# Aux_Board_V3.net
KiCad netlist of a schematic drawn in EAGLE
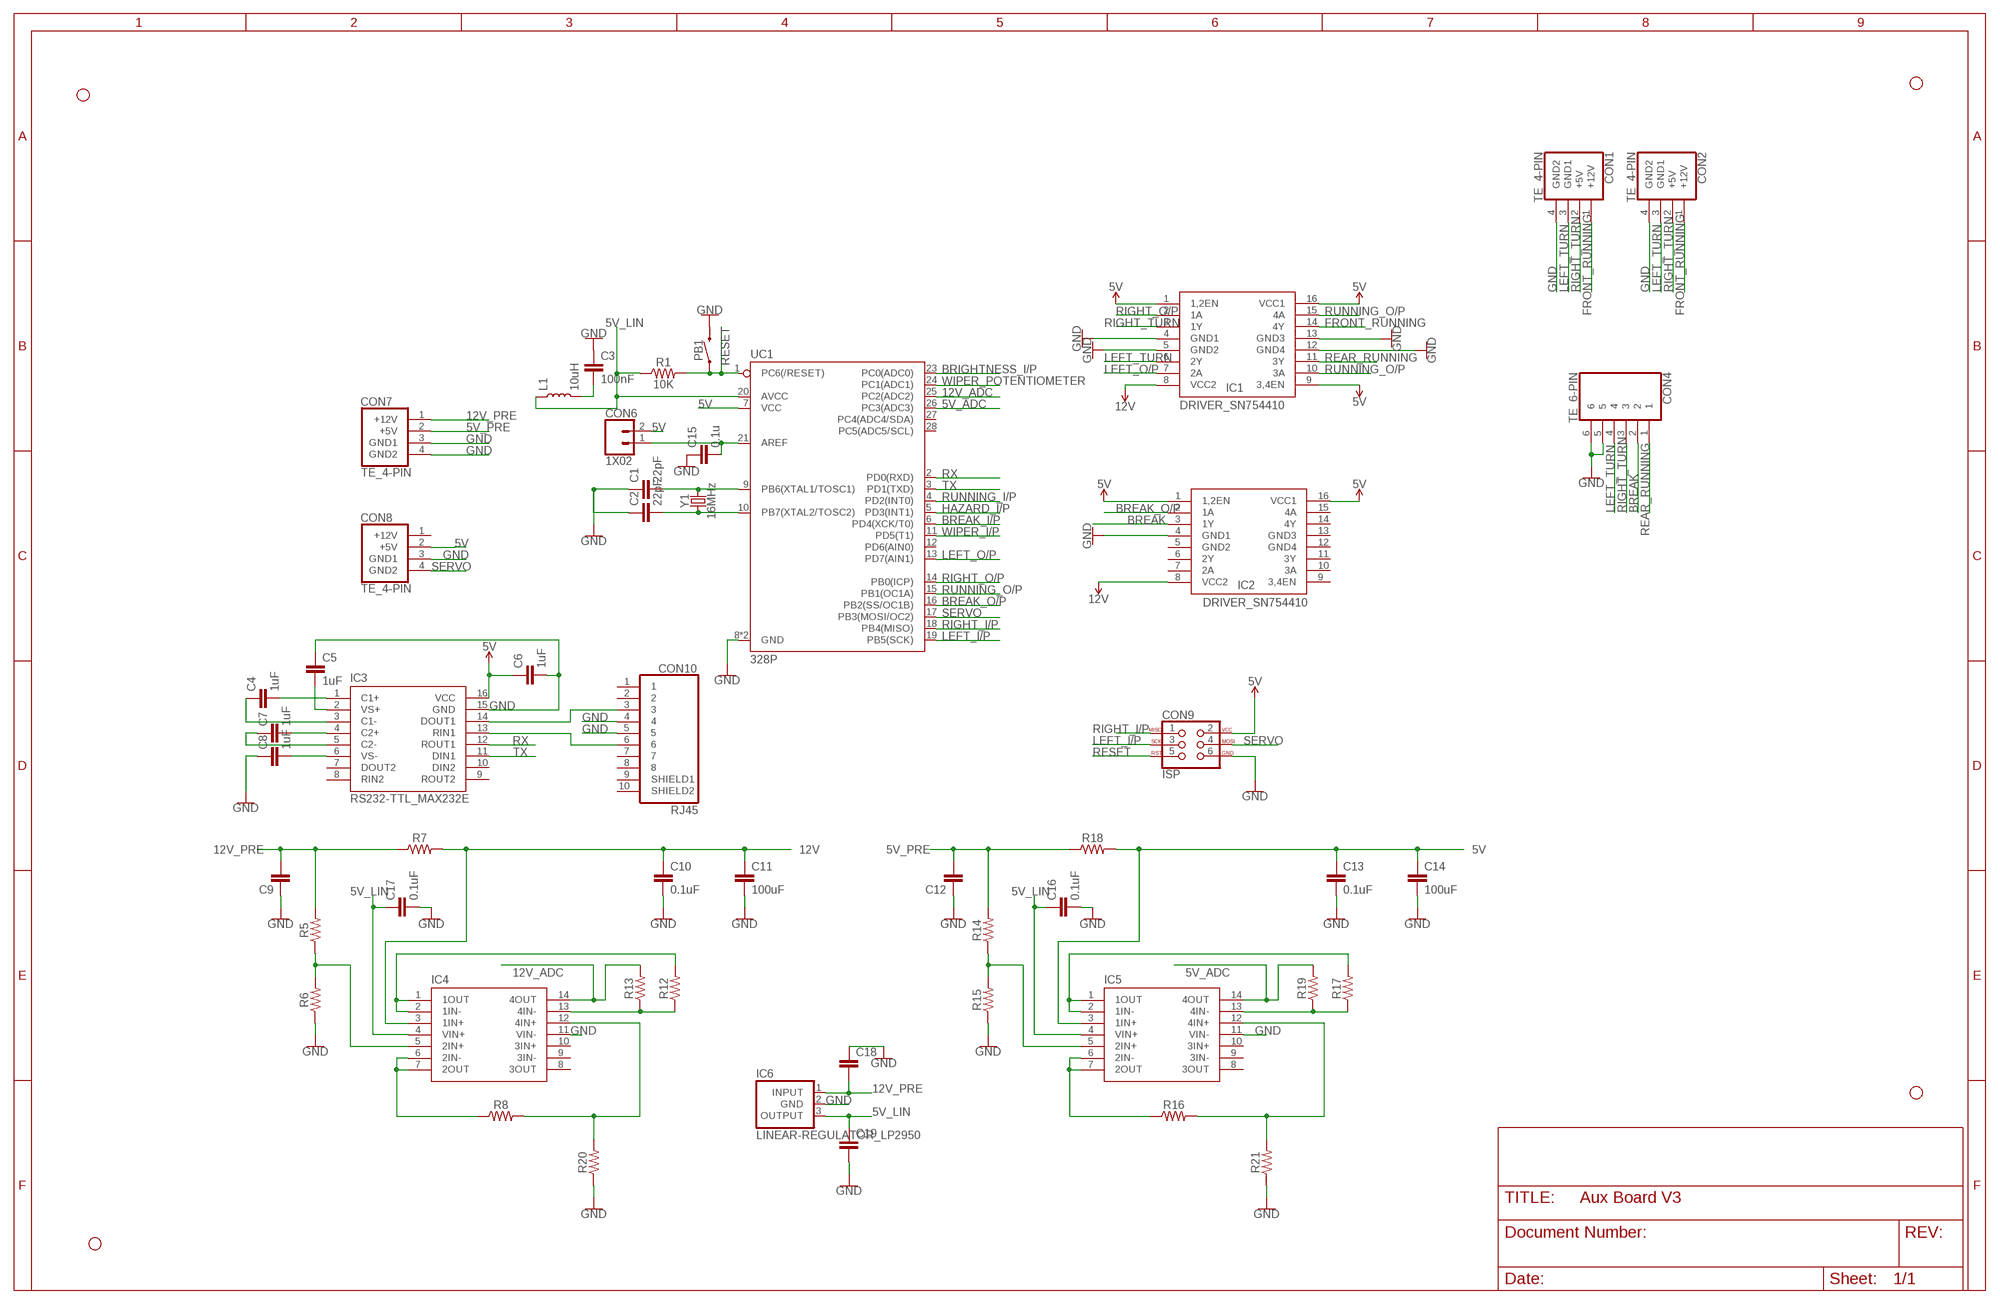
[diagram p0: schematic, sheet 1]

(export (version "E")
  (design (tool "Eeschema 10.0.6"))
  (components
    (comp (ref "C1")
      (value "22pF")
      (footprint "eagle-import:0805")
      (libsource (lib "eagle-import") (part "CAPACITOR_0805"))
    )
    (comp (ref "C2")
      (value "22pF")
      (footprint "eagle-import:0805")
      (libsource (lib "eagle-import") (part "CAPACITOR_0805"))
    )
    (comp (ref "C3")
      (value "100nF")
      (footprint "eagle-import:0805")
      (libsource (lib "eagle-import") (part "CAPACITOR_0805"))
    )
    (comp (ref "C4")
      (value "1uF")
      (footprint "eagle-import:0805")
      (libsource (lib "eagle-import") (part "CAPACITOR_0805"))
    )
    (comp (ref "C5")
      (value "1uF")
      (footprint "eagle-import:0805")
      (libsource (lib "eagle-import") (part "CAPACITOR_0805"))
    )
    (comp (ref "C6")
      (value "1uF")
      (footprint "eagle-import:0805")
      (libsource (lib "eagle-import") (part "CAPACITOR_0805"))
    )
    (comp (ref "C7")
      (value "1uF")
      (footprint "eagle-import:0805")
      (libsource (lib "eagle-import") (part "CAPACITOR_0805"))
    )
    (comp (ref "C8")
      (value "1uF")
      (footprint "eagle-import:0805")
      (libsource (lib "eagle-import") (part "CAPACITOR_0805"))
    )
    (comp (ref "C9")
      (value "CAPACITOR_0805")
      (footprint "eagle-import:0805")
      (libsource (lib "eagle-import") (part "CAPACITOR_0805"))
    )
    (comp (ref "C10")
      (value "0.1uF")
      (footprint "eagle-import:0805")
      (libsource (lib "eagle-import") (part "CAPACITOR_0805"))
    )
    (comp (ref "C11")
      (value "100uF")
      (footprint "eagle-import:0805")
      (libsource (lib "eagle-import") (part "CAPACITOR_0805"))
    )
    (comp (ref "C12")
      (value "CAPACITOR_0805")
      (footprint "eagle-import:0805")
      (libsource (lib "eagle-import") (part "CAPACITOR_0805"))
    )
    (comp (ref "C13")
      (value "0.1uF")
      (footprint "eagle-import:0805")
      (libsource (lib "eagle-import") (part "CAPACITOR_0805"))
    )
    (comp (ref "C14")
      (value "100uF")
      (footprint "eagle-import:0805")
      (libsource (lib "eagle-import") (part "CAPACITOR_0805"))
    )
    (comp (ref "C15")
      (value "0.1u")
      (footprint "eagle-import:0805")
      (libsource (lib "eagle-import") (part "CAPACITOR_0805"))
    )
    (comp (ref "C16")
      (value "0.1uF")
      (footprint "eagle-import:0805")
      (libsource (lib "eagle-import") (part "CAPACITOR_0805"))
    )
    (comp (ref "C17")
      (value "0.1uF")
      (footprint "eagle-import:0805")
      (libsource (lib "eagle-import") (part "CAPACITOR_0805"))
    )
    (comp (ref "C18")
      (value "CAPACITOR_0805")
      (footprint "eagle-import:0805")
      (libsource (lib "eagle-import") (part "CAPACITOR_0805"))
    )
    (comp (ref "C19")
      (value "CAPACITOR_0805")
      (footprint "eagle-import:0805")
      (libsource (lib "eagle-import") (part "CAPACITOR_0805"))
    )
    (comp (ref "CON1")
      (value "TE_4-PIN")
      (footprint "eagle-import:TE_4-PIN")
      (libsource (lib "eagle-import") (part "TE_4-PIN"))
    )
    (comp (ref "CON2")
      (value "TE_4-PIN")
      (footprint "eagle-import:TE_4-PIN")
      (libsource (lib "eagle-import") (part "TE_4-PIN"))
    )
    (comp (ref "CON4")
      (value "TE_6-PIN")
      (footprint "eagle-import:TE_6-PIN")
      (libsource (lib "eagle-import") (part "TE_6-PIN"))
    )
    (comp (ref "CON6")
      (value "1X02")
      (footprint "eagle-import:1X02")
      (libsource (lib "eagle-import") (part "1X02"))
    )
    (comp (ref "CON7")
      (value "TE_4-PIN")
      (footprint "eagle-import:TE_4-PIN")
      (libsource (lib "eagle-import") (part "TE_4-PIN"))
    )
    (comp (ref "CON8")
      (value "TE_4-PIN")
      (footprint "eagle-import:TE_4-PIN")
      (libsource (lib "eagle-import") (part "TE_4-PIN"))
    )
    (comp (ref "CON9")
      (value "ISP")
      (footprint "eagle-import:ISP_CONNECTOR")
      (libsource (lib "eagle-import") (part "ISP"))
    )
    (comp (ref "CON10")
      (value "RJ45")
      (footprint "eagle-import:RJ45")
      (libsource (lib "eagle-import") (part "RJ45"))
    )
    (comp (ref "H1")
      (value "STAND-OFF")
      (footprint "eagle-import:STAND-OFF")
      (libsource (lib "eagle-import") (part "STAND-OFF"))
    )
    (comp (ref "H2")
      (value "STAND-OFF")
      (footprint "eagle-import:STAND-OFF")
      (libsource (lib "eagle-import") (part "STAND-OFF"))
    )
    (comp (ref "H3")
      (value "STAND-OFF")
      (footprint "eagle-import:STAND-OFF")
      (libsource (lib "eagle-import") (part "STAND-OFF"))
    )
    (comp (ref "H4")
      (value "STAND-OFF")
      (footprint "eagle-import:STAND-OFF")
      (libsource (lib "eagle-import") (part "STAND-OFF"))
    )
    (comp (ref "IC1")
      (value "DRIVER_SN754410")
      (footprint "eagle-import:DIP16")
      (libsource (lib "eagle-import") (part "DRIVER_SN754410"))
    )
    (comp (ref "IC2")
      (value "DRIVER_SN754410")
      (footprint "eagle-import:DIP16")
      (libsource (lib "eagle-import") (part "DRIVER_SN754410"))
    )
    (comp (ref "IC3")
      (value "RS232-TTL_MAX232E")
      (footprint "eagle-import:DIP16")
      (libsource (lib "eagle-import") (part "RS232-TTL_MAX232E"))
    )
    (comp (ref "IC4")
      (value "OP-AMP_QUAD")
      (footprint "eagle-import:DIP14")
      (libsource (lib "eagle-import") (part "OP-AMP_QUAD"))
    )
    (comp (ref "IC5")
      (value "OP-AMP_QUAD")
      (footprint "eagle-import:DIP14")
      (libsource (lib "eagle-import") (part "OP-AMP_QUAD"))
    )
    (comp (ref "IC6")
      (value "LINEAR-REGULATOR_LP2950")
      (footprint "eagle-import:TO92")
      (libsource (lib "eagle-import") (part "LINEAR-REGULATOR_LP2950"))
    )
    (comp (ref "L1")
      (value "10uH")
      (footprint "eagle-import:0805")
      (libsource (lib "eagle-import") (part "INDUCTOR_0805"))
    )
    (comp (ref "PB1")
      (value "PUSHBUTTON")
      (footprint "eagle-import:PUSHBUTTON")
      (libsource (lib "eagle-import") (part "PUSHBUTTON"))
    )
    (comp (ref "R1")
      (value "10K")
      (footprint "eagle-import:0805")
      (libsource (lib "eagle-import") (part "RESISTOR_0805"))
    )
    (comp (ref "R5")
      (value "RESISTOR_0805")
      (footprint "eagle-import:0805")
      (libsource (lib "eagle-import") (part "RESISTOR_0805"))
    )
    (comp (ref "R6")
      (value "RESISTOR_0805")
      (footprint "eagle-import:0805")
      (libsource (lib "eagle-import") (part "RESISTOR_0805"))
    )
    (comp (ref "R7")
      (value "RESISTOR_1210")
      (footprint "eagle-import:1210")
      (libsource (lib "eagle-import") (part "RESISTOR_1210"))
    )
    (comp (ref "R8")
      (value "RESISTOR_0805")
      (footprint "eagle-import:0805")
      (libsource (lib "eagle-import") (part "RESISTOR_0805"))
    )
    (comp (ref "R12")
      (value "RESISTOR_0805")
      (footprint "eagle-import:0805")
      (libsource (lib "eagle-import") (part "RESISTOR_0805"))
    )
    (comp (ref "R13")
      (value "RESISTOR_0805")
      (footprint "eagle-import:0805")
      (libsource (lib "eagle-import") (part "RESISTOR_0805"))
    )
    (comp (ref "R14")
      (value "RESISTOR_0805")
      (footprint "eagle-import:0805")
      (libsource (lib "eagle-import") (part "RESISTOR_0805"))
    )
    (comp (ref "R15")
      (value "RESISTOR_0805")
      (footprint "eagle-import:0805")
      (libsource (lib "eagle-import") (part "RESISTOR_0805"))
    )
    (comp (ref "R16")
      (value "RESISTOR_0805")
      (footprint "eagle-import:0805")
      (libsource (lib "eagle-import") (part "RESISTOR_0805"))
    )
    (comp (ref "R17")
      (value "RESISTOR_0805")
      (footprint "eagle-import:0805")
      (libsource (lib "eagle-import") (part "RESISTOR_0805"))
    )
    (comp (ref "R18")
      (value "RESISTOR_1210")
      (footprint "eagle-import:1210")
      (libsource (lib "eagle-import") (part "RESISTOR_1210"))
    )
    (comp (ref "R19")
      (value "RESISTOR_0805")
      (footprint "eagle-import:0805")
      (libsource (lib "eagle-import") (part "RESISTOR_0805"))
    )
    (comp (ref "R20")
      (value "RESISTOR_0805")
      (footprint "eagle-import:0805")
      (libsource (lib "eagle-import") (part "RESISTOR_0805"))
    )
    (comp (ref "R21")
      (value "RESISTOR_0805")
      (footprint "eagle-import:0805")
      (libsource (lib "eagle-import") (part "RESISTOR_0805"))
    )
    (comp (ref "UC1")
      (value "328P")
      (footprint "eagle-import:DIP28")
      (libsource (lib "eagle-import") (part "ATMEGA328P_DIP28"))
    )
    (comp (ref "Y1")
      (value "16MHz")
      (footprint "eagle-import:HC49US")
      (libsource (lib "eagle-import") (part "CRYSTAL-16MHZPTH-HC49US"))
    )
  )
  (nets
    (net (code "1") (name "/5V_ADC") (class "Default")
      (node (ref "IC5") (pin "14") (pinfunction "4OUT_14") (pintype "bidirectional"))
      (node (ref "R19") (pin "2") (pinfunction "2_2") (pintype "passive"))
      (node (ref "UC1") (pin "26") (pinfunction "PC3(ADC3)_26") (pintype "bidirectional"))
    )
    (net (code "2") (name "/5V_LIN") (class "Default")
      (node (ref "C16") (pin "1") (pinfunction "1_1") (pintype "passive"))
      (node (ref "C17") (pin "1") (pinfunction "1_1") (pintype "passive"))
      (node (ref "C19") (pin "1") (pinfunction "1_1") (pintype "passive"))
      (node (ref "IC4") (pin "4") (pinfunction "VIN+_4") (pintype "bidirectional"))
      (node (ref "IC5") (pin "4") (pinfunction "VIN+_4") (pintype "bidirectional"))
      (node (ref "IC6") (pin "3") (pinfunction "OUTPUT_3") (pintype "bidirectional"))
      (node (ref "L1") (pin "1") (pinfunction "1_1") (pintype "passive"))
      (node (ref "R1") (pin "1") (pinfunction "1_1") (pintype "passive"))
      (node (ref "UC1") (pin "20") (pinfunction "AVCC_20") (pintype "bidirectional"))
    )
    (net (code "3") (name "/5V_PRE") (class "Default")
      (node (ref "C12") (pin "2") (pinfunction "2_2") (pintype "passive"))
      (node (ref "CON7") (pin "2") (pinfunction "+5V_2") (pintype "passive"))
      (node (ref "R14") (pin "2") (pinfunction "2_2") (pintype "passive"))
      (node (ref "R18") (pin "1") (pinfunction "1_1") (pintype "passive"))
    )
    (net (code "4") (name "/12V_ADC") (class "Default")
      (node (ref "IC4") (pin "14") (pinfunction "4OUT_14") (pintype "bidirectional"))
      (node (ref "R13") (pin "2") (pinfunction "2_2") (pintype "passive"))
      (node (ref "UC1") (pin "25") (pinfunction "PC2(ADC2)_25") (pintype "bidirectional"))
    )
    (net (code "5") (name "/12V_PRE") (class "Default")
      (node (ref "C18") (pin "2") (pinfunction "2_2") (pintype "passive"))
      (node (ref "C9") (pin "2") (pinfunction "2_2") (pintype "passive"))
      (node (ref "CON7") (pin "1") (pinfunction "+12V_1") (pintype "passive"))
      (node (ref "IC6") (pin "1") (pinfunction "INPUT_1") (pintype "bidirectional"))
      (node (ref "R5") (pin "2") (pinfunction "2_2") (pintype "passive"))
      (node (ref "R7") (pin "1") (pinfunction "1_1") (pintype "passive"))
    )
    (net (code "6") (name "/BREAK") (class "Default")
      (node (ref "CON4") (pin "2") (pinfunction "2_2") (pintype "passive"))
      (node (ref "IC2") (pin "3") (pinfunction "1Y_3") (pintype "bidirectional"))
    )
    (net (code "7") (name "/BREAK_I{slash}P") (class "Default")
      (node (ref "UC1") (pin "6") (pinfunction "PD4(XCK/T0)_6") (pintype "bidirectional"))
    )
    (net (code "8") (name "/BREAK_O{slash}P") (class "Default")
      (node (ref "IC2") (pin "2") (pinfunction "1A_2") (pintype "bidirectional"))
      (node (ref "UC1") (pin "16") (pinfunction "PB2(SS/OC1B)_16") (pintype "bidirectional"))
    )
    (net (code "9") (name "/BRIGHTNESS_I{slash}P") (class "Default")
      (node (ref "UC1") (pin "23") (pinfunction "PC0(ADC0)_23") (pintype "bidirectional"))
    )
    (net (code "10") (name "/FRONT_RUNNING") (class "Default")
      (node (ref "CON1") (pin "1") (pinfunction "+12V_1") (pintype "passive"))
      (node (ref "CON2") (pin "1") (pinfunction "+12V_1") (pintype "passive"))
      (node (ref "IC1") (pin "14") (pinfunction "4Y_14") (pintype "bidirectional"))
    )
    (net (code "11") (name "/HAZARD_I{slash}P") (class "Default")
      (node (ref "UC1") (pin "5") (pinfunction "PD3(INT1)_5") (pintype "bidirectional"))
    )
    (net (code "12") (name "/LEFT_I{slash}P") (class "Default")
      (node (ref "CON9") (pin "3") (pinfunction "3_3") (pintype "passive"))
      (node (ref "UC1") (pin "19") (pinfunction "PB5(SCK)_19") (pintype "bidirectional"))
    )
    (net (code "13") (name "/LEFT_O{slash}P") (class "Default")
      (node (ref "IC1") (pin "7") (pinfunction "2A_7") (pintype "bidirectional"))
      (node (ref "UC1") (pin "13") (pinfunction "PD7(AIN1)_13") (pintype "bidirectional"))
    )
    (net (code "14") (name "/LEFT_TURN") (class "Default")
      (node (ref "CON1") (pin "3") (pinfunction "GND1_3") (pintype "passive"))
      (node (ref "CON2") (pin "3") (pinfunction "GND1_3") (pintype "passive"))
      (node (ref "CON4") (pin "4") (pinfunction "4_4") (pintype "passive"))
      (node (ref "IC1") (pin "6") (pinfunction "2Y_6") (pintype "bidirectional"))
    )
    (net (code "15") (name "/REAR_RUNNING") (class "Default")
      (node (ref "CON4") (pin "1") (pinfunction "1_1") (pintype "passive"))
      (node (ref "IC1") (pin "11") (pinfunction "3Y_11") (pintype "bidirectional"))
    )
    (net (code "16") (name "/RESET") (class "Default")
      (node (ref "CON9") (pin "5") (pinfunction "5_5") (pintype "passive"))
      (node (ref "PB1") (pin "1") (pinfunction "1_1") (pintype "passive"))
      (node (ref "PB1") (pin "2") (pinfunction "1_2") (pintype "passive"))
      (node (ref "R1") (pin "2") (pinfunction "2_2") (pintype "passive"))
      (node (ref "UC1") (pin "1") (pinfunction "PC6(/RESET)_1") (pintype "bidirectional"))
    )
    (net (code "17") (name "/RIGHT_I{slash}P") (class "Default")
      (node (ref "CON9") (pin "1") (pinfunction "1_1") (pintype "passive"))
      (node (ref "UC1") (pin "18") (pinfunction "PB4(MISO)_18") (pintype "bidirectional"))
    )
    (net (code "18") (name "/RIGHT_O{slash}P") (class "Default")
      (node (ref "IC1") (pin "2") (pinfunction "1A_2") (pintype "bidirectional"))
      (node (ref "UC1") (pin "14") (pinfunction "PB0(ICP)_14") (pintype "bidirectional"))
    )
    (net (code "19") (name "/RIGHT_TURN") (class "Default")
      (node (ref "CON1") (pin "2") (pinfunction "+5V_2") (pintype "passive"))
      (node (ref "CON2") (pin "2") (pinfunction "+5V_2") (pintype "passive"))
      (node (ref "CON4") (pin "3") (pinfunction "3_3") (pintype "passive"))
      (node (ref "IC1") (pin "3") (pinfunction "1Y_3") (pintype "bidirectional"))
    )
    (net (code "20") (name "/RUNNING_I{slash}P") (class "Default")
      (node (ref "UC1") (pin "4") (pinfunction "PD2(INT0)_4") (pintype "bidirectional"))
    )
    (net (code "21") (name "/RUNNING_O{slash}P") (class "Default")
      (node (ref "IC1") (pin "10") (pinfunction "3A_10") (pintype "bidirectional"))
      (node (ref "IC1") (pin "15") (pinfunction "4A_15") (pintype "bidirectional"))
      (node (ref "UC1") (pin "15") (pinfunction "PB1(OC1A)_15") (pintype "bidirectional"))
    )
    (net (code "22") (name "/RX") (class "Default")
      (node (ref "IC3") (pin "12") (pinfunction "ROUT1_12") (pintype "bidirectional"))
      (node (ref "UC1") (pin "2") (pinfunction "PD0(RXD)_2") (pintype "bidirectional"))
    )
    (net (code "23") (name "/SERVO") (class "Default")
      (node (ref "CON8") (pin "4") (pinfunction "GND2_4") (pintype "passive"))
      (node (ref "CON9") (pin "4") (pinfunction "4_4") (pintype "passive"))
      (node (ref "UC1") (pin "17") (pinfunction "PB3(MOSI/OC2)_17") (pintype "bidirectional"))
    )
    (net (code "24") (name "/TX") (class "Default")
      (node (ref "IC3") (pin "11") (pinfunction "DIN1_11") (pintype "bidirectional"))
      (node (ref "UC1") (pin "3") (pinfunction "PD1(TXD)_3") (pintype "bidirectional"))
    )
    (net (code "25") (name "/WIPER_I{slash}P") (class "Default")
      (node (ref "UC1") (pin "11") (pinfunction "PD5(T1)_11") (pintype "bidirectional"))
    )
    (net (code "26") (name "/WIPER_POTENTIOMETER") (class "Default")
      (node (ref "UC1") (pin "24") (pinfunction "PC1(ADC1)_24") (pintype "bidirectional"))
    )
    (net (code "27") (name "5V") (class "Default")
      (node (ref "C13") (pin "1") (pinfunction "1_1") (pintype "passive"))
      (node (ref "C14") (pin "1") (pinfunction "1_1") (pintype "passive"))
      (node (ref "C15") (pin "2") (pinfunction "2_2") (pintype "passive"))
      (node (ref "C6") (pin "1") (pinfunction "1_1") (pintype "passive"))
      (node (ref "CON6") (pin "1") (pinfunction "1_1") (pintype "passive"))
      (node (ref "CON6") (pin "2") (pinfunction "2_2") (pintype "passive"))
      (node (ref "CON8") (pin "2") (pinfunction "+5V_2") (pintype "passive"))
      (node (ref "CON9") (pin "2") (pinfunction "2_2") (pintype "passive"))
      (node (ref "IC1") (pin "1") (pinfunction "1,2EN_1") (pintype "bidirectional"))
      (node (ref "IC1") (pin "16") (pinfunction "VCC1_16") (pintype "bidirectional"))
      (node (ref "IC1") (pin "9") (pinfunction "3,4EN_9") (pintype "bidirectional"))
      (node (ref "IC2") (pin "1") (pinfunction "1,2EN_1") (pintype "bidirectional"))
      (node (ref "IC2") (pin "16") (pinfunction "VCC1_16") (pintype "bidirectional"))
      (node (ref "IC3") (pin "16") (pinfunction "VCC_16") (pintype "bidirectional"))
      (node (ref "IC5") (pin "3") (pinfunction "1IN+_3") (pintype "bidirectional"))
      (node (ref "R18") (pin "2") (pinfunction "2_2") (pintype "passive"))
      (node (ref "UC1") (pin "21") (pinfunction "AREF_21") (pintype "bidirectional"))
      (node (ref "UC1") (pin "7") (pinfunction "VCC_7") (pintype "bidirectional"))
    )
    (net (code "28") (name "12V") (class "Default")
      (node (ref "C10") (pin "1") (pinfunction "1_1") (pintype "passive"))
      (node (ref "C11") (pin "1") (pinfunction "1_1") (pintype "passive"))
      (node (ref "IC1") (pin "8") (pinfunction "VCC2_8") (pintype "bidirectional"))
      (node (ref "IC2") (pin "8") (pinfunction "VCC2_8") (pintype "bidirectional"))
      (node (ref "IC4") (pin "3") (pinfunction "1IN+_3") (pintype "bidirectional"))
      (node (ref "R7") (pin "2") (pinfunction "2_2") (pintype "passive"))
    )
    (net (code "29") (name "GND") (class "Default")
      (node (ref "C1") (pin "1") (pinfunction "1_1") (pintype "passive"))
      (node (ref "C10") (pin "2") (pinfunction "2_2") (pintype "passive"))
      (node (ref "C11") (pin "2") (pinfunction "2_2") (pintype "passive"))
      (node (ref "C12") (pin "1") (pinfunction "1_1") (pintype "passive"))
      (node (ref "C13") (pin "2") (pinfunction "2_2") (pintype "passive"))
      (node (ref "C14") (pin "2") (pinfunction "2_2") (pintype "passive"))
      (node (ref "C15") (pin "1") (pinfunction "1_1") (pintype "passive"))
      (node (ref "C16") (pin "2") (pinfunction "2_2") (pintype "passive"))
      (node (ref "C17") (pin "2") (pinfunction "2_2") (pintype "passive"))
      (node (ref "C18") (pin "1") (pinfunction "1_1") (pintype "passive"))
      (node (ref "C19") (pin "2") (pinfunction "2_2") (pintype "passive"))
      (node (ref "C2") (pin "1") (pinfunction "1_1") (pintype "passive"))
      (node (ref "C3") (pin "1") (pinfunction "1_1") (pintype "passive"))
      (node (ref "C5") (pin "1") (pinfunction "1_1") (pintype "passive"))
      (node (ref "C6") (pin "2") (pinfunction "2_2") (pintype "passive"))
      (node (ref "C8") (pin "1") (pinfunction "1_1") (pintype "passive"))
      (node (ref "C9") (pin "1") (pinfunction "1_1") (pintype "passive"))
      (node (ref "CON1") (pin "4") (pinfunction "GND2_4") (pintype "passive"))
      (node (ref "CON10") (pin "4") (pinfunction "4_4") (pintype "passive"))
      (node (ref "CON10") (pin "5") (pinfunction "5_5") (pintype "passive"))
      (node (ref "CON2") (pin "4") (pinfunction "GND2_4") (pintype "passive"))
      (node (ref "CON4") (pin "5") (pinfunction "5_5") (pintype "passive"))
      (node (ref "CON4") (pin "6") (pinfunction "6_6") (pintype "passive"))
      (node (ref "CON7") (pin "3") (pinfunction "GND1_3") (pintype "passive"))
      (node (ref "CON7") (pin "4") (pinfunction "GND2_4") (pintype "passive"))
      (node (ref "CON8") (pin "3") (pinfunction "GND1_3") (pintype "passive"))
      (node (ref "CON9") (pin "6") (pinfunction "6_6") (pintype "passive"))
      (node (ref "IC1") (pin "12") (pinfunction "GND4_12") (pintype "bidirectional"))
      (node (ref "IC1") (pin "13") (pinfunction "GND3_13") (pintype "bidirectional"))
      (node (ref "IC1") (pin "4") (pinfunction "GND1_4") (pintype "bidirectional"))
      (node (ref "IC1") (pin "5") (pinfunction "GND2_5") (pintype "bidirectional"))
      (node (ref "IC2") (pin "4") (pinfunction "GND1_4") (pintype "bidirectional"))
      (node (ref "IC3") (pin "15") (pinfunction "GND_15") (pintype "bidirectional"))
      (node (ref "IC4") (pin "11") (pinfunction "VIN-_11") (pintype "bidirectional"))
      (node (ref "IC5") (pin "11") (pinfunction "VIN-_11") (pintype "bidirectional"))
      (node (ref "IC6") (pin "2") (pinfunction "GND_2") (pintype "bidirectional"))
      (node (ref "PB1") (pin "3") (pinfunction "2_3") (pintype "passive"))
      (node (ref "PB1") (pin "4") (pinfunction "2_4") (pintype "passive"))
      (node (ref "R15") (pin "1") (pinfunction "1_1") (pintype "passive"))
      (node (ref "R20") (pin "1") (pinfunction "1_1") (pintype "passive"))
      (node (ref "R21") (pin "1") (pinfunction "1_1") (pintype "passive"))
      (node (ref "R6") (pin "1") (pinfunction "1_1") (pintype "passive"))
      (node (ref "UC1") (pin "22") (pinfunction "GND_22") (pintype "bidirectional"))
      (node (ref "UC1") (pin "8") (pinfunction "GND_8") (pintype "bidirectional"))
    )
    (net (code "30") (name "Net-(C3-Pad2)") (class "Default")
      (node (ref "C3") (pin "2") (pinfunction "2_2") (pintype "passive"))
      (node (ref "L1") (pin "2") (pinfunction "2_2") (pintype "passive"))
    )
    (net (code "31") (name "Net-(IC3-C1+)") (class "Default")
      (node (ref "C4") (pin "2") (pinfunction "2_2") (pintype "passive"))
      (node (ref "IC3") (pin "1") (pinfunction "C1+_1") (pintype "bidirectional"))
    )
    (net (code "32") (name "Net-(IC3-C1-)") (class "Default")
      (node (ref "C4") (pin "1") (pinfunction "1_1") (pintype "passive"))
      (node (ref "IC3") (pin "3") (pinfunction "C1-_3") (pintype "bidirectional"))
    )
    (net (code "33") (name "Net-(IC3-C2+)") (class "Default")
      (node (ref "C7") (pin "2") (pinfunction "2_2") (pintype "passive"))
      (node (ref "IC3") (pin "4") (pinfunction "C2+_4") (pintype "bidirectional"))
    )
    (net (code "34") (name "Net-(IC3-C2-)") (class "Default")
      (node (ref "C7") (pin "1") (pinfunction "1_1") (pintype "passive"))
      (node (ref "IC3") (pin "5") (pinfunction "C2-_5") (pintype "bidirectional"))
    )
    (net (code "35") (name "Net-(IC3-DOUT1)") (class "Default")
      (node (ref "CON10") (pin "3") (pinfunction "3_3") (pintype "passive"))
      (node (ref "IC3") (pin "14") (pinfunction "DOUT1_14") (pintype "bidirectional"))
    )
    (net (code "36") (name "Net-(IC3-RIN1)") (class "Default")
      (node (ref "CON10") (pin "6") (pinfunction "6_6") (pintype "passive"))
      (node (ref "IC3") (pin "13") (pinfunction "RIN1_13") (pintype "bidirectional"))
    )
    (net (code "37") (name "Net-(IC3-VS+)") (class "Default")
      (node (ref "C5") (pin "2") (pinfunction "2_2") (pintype "passive"))
      (node (ref "IC3") (pin "2") (pinfunction "VS+_2") (pintype "bidirectional"))
    )
    (net (code "38") (name "Net-(IC3-VS-)") (class "Default")
      (node (ref "C8") (pin "2") (pinfunction "2_2") (pintype "passive"))
      (node (ref "IC3") (pin "6") (pinfunction "VS-_6") (pintype "bidirectional"))
    )
    (net (code "39") (name "Net-(IC4-1IN-)") (class "Default")
      (node (ref "IC4") (pin "1") (pinfunction "1OUT_1") (pintype "bidirectional"))
      (node (ref "IC4") (pin "2") (pinfunction "1IN-_2") (pintype "bidirectional"))
      (node (ref "R12") (pin "2") (pinfunction "2_2") (pintype "passive"))
    )
    (net (code "40") (name "Net-(IC4-2IN+)") (class "Default")
      (node (ref "IC4") (pin "5") (pinfunction "2IN+_5") (pintype "bidirectional"))
      (node (ref "R5") (pin "1") (pinfunction "1_1") (pintype "passive"))
      (node (ref "R6") (pin "2") (pinfunction "2_2") (pintype "passive"))
    )
    (net (code "41") (name "Net-(IC4-2IN-)") (class "Default")
      (node (ref "IC4") (pin "6") (pinfunction "2IN-_6") (pintype "bidirectional"))
      (node (ref "IC4") (pin "7") (pinfunction "2OUT_7") (pintype "bidirectional"))
      (node (ref "R8") (pin "1") (pinfunction "1_1") (pintype "passive"))
    )
    (net (code "42") (name "Net-(IC4-4IN+)") (class "Default")
      (node (ref "IC4") (pin "12") (pinfunction "4IN+_12") (pintype "bidirectional"))
      (node (ref "R20") (pin "2") (pinfunction "2_2") (pintype "passive"))
      (node (ref "R8") (pin "2") (pinfunction "2_2") (pintype "passive"))
    )
    (net (code "43") (name "Net-(IC4-4IN-)") (class "Default")
      (node (ref "IC4") (pin "13") (pinfunction "4IN-_13") (pintype "bidirectional"))
      (node (ref "R12") (pin "1") (pinfunction "1_1") (pintype "passive"))
      (node (ref "R13") (pin "1") (pinfunction "1_1") (pintype "passive"))
    )
    (net (code "44") (name "Net-(IC5-1IN-)") (class "Default")
      (node (ref "IC5") (pin "1") (pinfunction "1OUT_1") (pintype "bidirectional"))
      (node (ref "IC5") (pin "2") (pinfunction "1IN-_2") (pintype "bidirectional"))
      (node (ref "R17") (pin "2") (pinfunction "2_2") (pintype "passive"))
    )
    (net (code "45") (name "Net-(IC5-2IN+)") (class "Default")
      (node (ref "IC5") (pin "5") (pinfunction "2IN+_5") (pintype "bidirectional"))
      (node (ref "R14") (pin "1") (pinfunction "1_1") (pintype "passive"))
      (node (ref "R15") (pin "2") (pinfunction "2_2") (pintype "passive"))
    )
    (net (code "46") (name "Net-(IC5-2IN-)") (class "Default")
      (node (ref "IC5") (pin "6") (pinfunction "2IN-_6") (pintype "bidirectional"))
      (node (ref "IC5") (pin "7") (pinfunction "2OUT_7") (pintype "bidirectional"))
      (node (ref "R16") (pin "1") (pinfunction "1_1") (pintype "passive"))
    )
    (net (code "47") (name "Net-(IC5-4IN+)") (class "Default")
      (node (ref "IC5") (pin "12") (pinfunction "4IN+_12") (pintype "bidirectional"))
      (node (ref "R16") (pin "2") (pinfunction "2_2") (pintype "passive"))
      (node (ref "R21") (pin "2") (pinfunction "2_2") (pintype "passive"))
    )
    (net (code "48") (name "Net-(IC5-4IN-)") (class "Default")
      (node (ref "IC5") (pin "13") (pinfunction "4IN-_13") (pintype "bidirectional"))
      (node (ref "R17") (pin "1") (pinfunction "1_1") (pintype "passive"))
      (node (ref "R19") (pin "1") (pinfunction "1_1") (pintype "passive"))
    )
    (net (code "49") (name "Net-(UC1-PB6(XTAL1{slash}TOSC1))") (class "Default")
      (node (ref "C1") (pin "2") (pinfunction "2_2") (pintype "passive"))
      (node (ref "UC1") (pin "9") (pinfunction "PB6(XTAL1/TOSC1)_9") (pintype "bidirectional"))
      (node (ref "Y1") (pin "2") (pinfunction "2_2") (pintype "passive"))
    )
    (net (code "50") (name "Net-(UC1-PB7(XTAL2{slash}TOSC2))") (class "Default")
      (node (ref "C2") (pin "2") (pinfunction "2_2") (pintype "passive"))
      (node (ref "UC1") (pin "10") (pinfunction "PB7(XTAL2/TOSC2)_10") (pintype "bidirectional"))
      (node (ref "Y1") (pin "1") (pinfunction "1_1") (pintype "passive"))
    )
    (net (code "51") (name "unconnected-(CON8-+12V-Pad1)") (class "Default")
      (node (ref "CON8") (pin "1") (pinfunction "+12V_1") (pintype "passive"))
    )
    (net (code "52") (name "unconnected-(CON10-Pad1)") (class "Default")
      (node (ref "CON10") (pin "1") (pinfunction "1_1") (pintype "passive"))
    )
    (net (code "53") (name "unconnected-(CON10-Pad2)") (class "Default")
      (node (ref "CON10") (pin "2") (pinfunction "2_2") (pintype "passive"))
    )
    (net (code "54") (name "unconnected-(CON10-Pad7)") (class "Default")
      (node (ref "CON10") (pin "7") (pinfunction "7_7") (pintype "passive"))
    )
    (net (code "55") (name "unconnected-(CON10-Pad8)") (class "Default")
      (node (ref "CON10") (pin "8") (pinfunction "8_8") (pintype "passive"))
    )
    (net (code "56") (name "unconnected-(CON10-SHIELD1-Pad9)") (class "Default")
      (node (ref "CON10") (pin "9") (pinfunction "SHIELD1_9") (pintype "passive"))
    )
    (net (code "57") (name "unconnected-(CON10-SHIELD2-Pad10)") (class "Default")
      (node (ref "CON10") (pin "10") (pinfunction "SHIELD2_10") (pintype "passive"))
    )
    (net (code "58") (name "unconnected-(IC2-2A-Pad7)") (class "Default")
      (node (ref "IC2") (pin "7") (pinfunction "2A_7") (pintype "bidirectional"))
    )
    (net (code "59") (name "unconnected-(IC2-2Y-Pad6)") (class "Default")
      (node (ref "IC2") (pin "6") (pinfunction "2Y_6") (pintype "bidirectional"))
    )
    (net (code "60") (name "unconnected-(IC2-3,4EN-Pad9)") (class "Default")
      (node (ref "IC2") (pin "9") (pinfunction "3,4EN_9") (pintype "bidirectional"))
    )
    (net (code "61") (name "unconnected-(IC2-3A-Pad10)") (class "Default")
      (node (ref "IC2") (pin "10") (pinfunction "3A_10") (pintype "bidirectional"))
    )
    (net (code "62") (name "unconnected-(IC2-3Y-Pad11)") (class "Default")
      (node (ref "IC2") (pin "11") (pinfunction "3Y_11") (pintype "bidirectional"))
    )
    (net (code "63") (name "unconnected-(IC2-4A-Pad15)") (class "Default")
      (node (ref "IC2") (pin "15") (pinfunction "4A_15") (pintype "bidirectional"))
    )
    (net (code "64") (name "unconnected-(IC2-4Y-Pad14)") (class "Default")
      (node (ref "IC2") (pin "14") (pinfunction "4Y_14") (pintype "bidirectional"))
    )
    (net (code "65") (name "unconnected-(IC2-GND2-Pad5)") (class "Default")
      (node (ref "IC2") (pin "5") (pinfunction "GND2_5") (pintype "bidirectional"))
    )
    (net (code "66") (name "unconnected-(IC2-GND3-Pad13)") (class "Default")
      (node (ref "IC2") (pin "13") (pinfunction "GND3_13") (pintype "bidirectional"))
    )
    (net (code "67") (name "unconnected-(IC2-GND4-Pad12)") (class "Default")
      (node (ref "IC2") (pin "12") (pinfunction "GND4_12") (pintype "bidirectional"))
    )
    (net (code "68") (name "unconnected-(IC3-DIN2-Pad10)") (class "Default")
      (node (ref "IC3") (pin "10") (pinfunction "DIN2_10") (pintype "bidirectional"))
    )
    (net (code "69") (name "unconnected-(IC3-DOUT2-Pad7)") (class "Default")
      (node (ref "IC3") (pin "7") (pinfunction "DOUT2_7") (pintype "bidirectional"))
    )
    (net (code "70") (name "unconnected-(IC3-RIN2-Pad8)") (class "Default")
      (node (ref "IC3") (pin "8") (pinfunction "RIN2_8") (pintype "bidirectional"))
    )
    (net (code "71") (name "unconnected-(IC3-ROUT2-Pad9)") (class "Default")
      (node (ref "IC3") (pin "9") (pinfunction "ROUT2_9") (pintype "bidirectional"))
    )
    (net (code "72") (name "unconnected-(IC4-3IN+-Pad10)") (class "Default")
      (node (ref "IC4") (pin "10") (pinfunction "3IN+_10") (pintype "bidirectional"))
    )
    (net (code "73") (name "unconnected-(IC4-3IN--Pad9)") (class "Default")
      (node (ref "IC4") (pin "9") (pinfunction "3IN-_9") (pintype "bidirectional"))
    )
    (net (code "74") (name "unconnected-(IC4-3OUT-Pad8)") (class "Default")
      (node (ref "IC4") (pin "8") (pinfunction "3OUT_8") (pintype "bidirectional"))
    )
    (net (code "75") (name "unconnected-(IC5-3IN+-Pad10)") (class "Default")
      (node (ref "IC5") (pin "10") (pinfunction "3IN+_10") (pintype "bidirectional"))
    )
    (net (code "76") (name "unconnected-(IC5-3IN--Pad9)") (class "Default")
      (node (ref "IC5") (pin "9") (pinfunction "3IN-_9") (pintype "bidirectional"))
    )
    (net (code "77") (name "unconnected-(IC5-3OUT-Pad8)") (class "Default")
      (node (ref "IC5") (pin "8") (pinfunction "3OUT_8") (pintype "bidirectional"))
    )
    (net (code "78") (name "unconnected-(UC1-PC4(ADC4{slash}SDA)-Pad27)") (class "Default")
      (node (ref "UC1") (pin "27") (pinfunction "PC4(ADC4/SDA)_27") (pintype "bidirectional"))
    )
    (net (code "79") (name "unconnected-(UC1-PC5(ADC5{slash}SCL)-Pad28)") (class "Default")
      (node (ref "UC1") (pin "28") (pinfunction "PC5(ADC5/SCL)_28") (pintype "bidirectional"))
    )
    (net (code "80") (name "unconnected-(UC1-PD6(AIN0)-Pad12)") (class "Default")
      (node (ref "UC1") (pin "12") (pinfunction "PD6(AIN0)_12") (pintype "bidirectional"))
    )
  )
)
